# Duty_cycle_BDD_2.net
KiCad netlist of a schematic drawn in Altium Designer
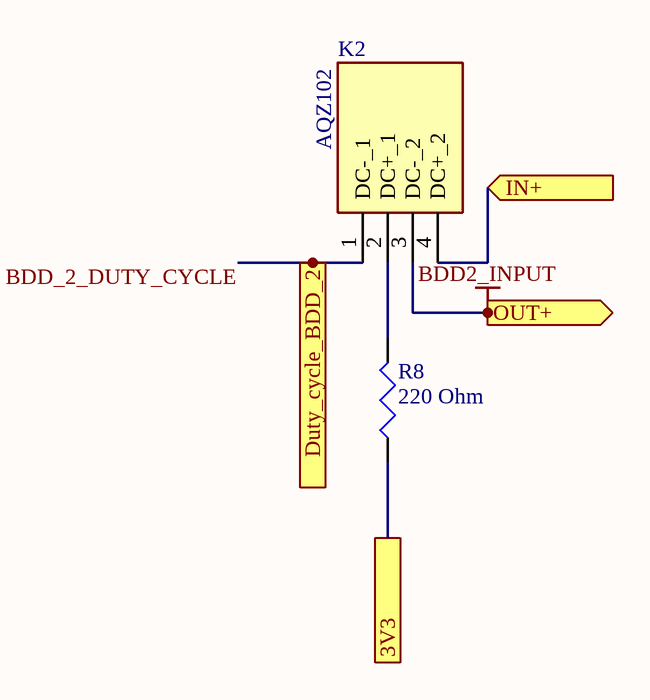
[diagram p0: Duty_cycle_BDD_2.SchDoc]

(export (version "E")
  (design (tool "Eeschema 10.0.6"))
  (components
    (comp (ref "K2")
      (value "AQZ102")
      (footprint "SamacSys:AQZ102")
      (description "Relay or Contactor")
      (fields (field (name "MOUSER PART NUMBER") "769-AQZ102"))
      (libsource (lib "*") (part "AQZ102"))
    )
    (comp (ref "R8")
      (value "220 Ohm")
      (footprint "J1-0603")
      (description "Resistor")
      (fields (field (name "PUBLISHER") "Altium Limited"))
      (libsource (lib "Miscellaneous Devices") (part "Res3"))
    )
  )
  (nets
    (net (code "1") (name "/3V3") (class "Default")
      (node (ref "R8") (pin "1") (pinfunction "1_1") (pintype "passive"))
    )
    (net (code "2") (name "/BDD_2_DUTY_CYCLE") (class "Default")
      (node (ref "K2") (pin "1") (pinfunction "DC-_1_1") (pintype "passive"))
    )
    (net (code "3") (name "/IN+") (class "Default")
      (node (ref "K2") (pin "4") (pinfunction "DC+_2_4") (pintype "passive"))
    )
    (net (code "4") (name "BDD2_INPUT") (class "Default")
      (node (ref "K2") (pin "3") (pinfunction "DC-_2_3") (pintype "passive"))
    )
    (net (code "5") (name "Net-(K2-DC+_1)") (class "Default")
      (node (ref "K2") (pin "2") (pinfunction "DC+_1_2") (pintype "passive"))
      (node (ref "R8") (pin "2") (pinfunction "2_2") (pintype "passive"))
    )
  )
)
